# SCH_PWR.net
KiCad netlist of a schematic drawn in Altium Designer
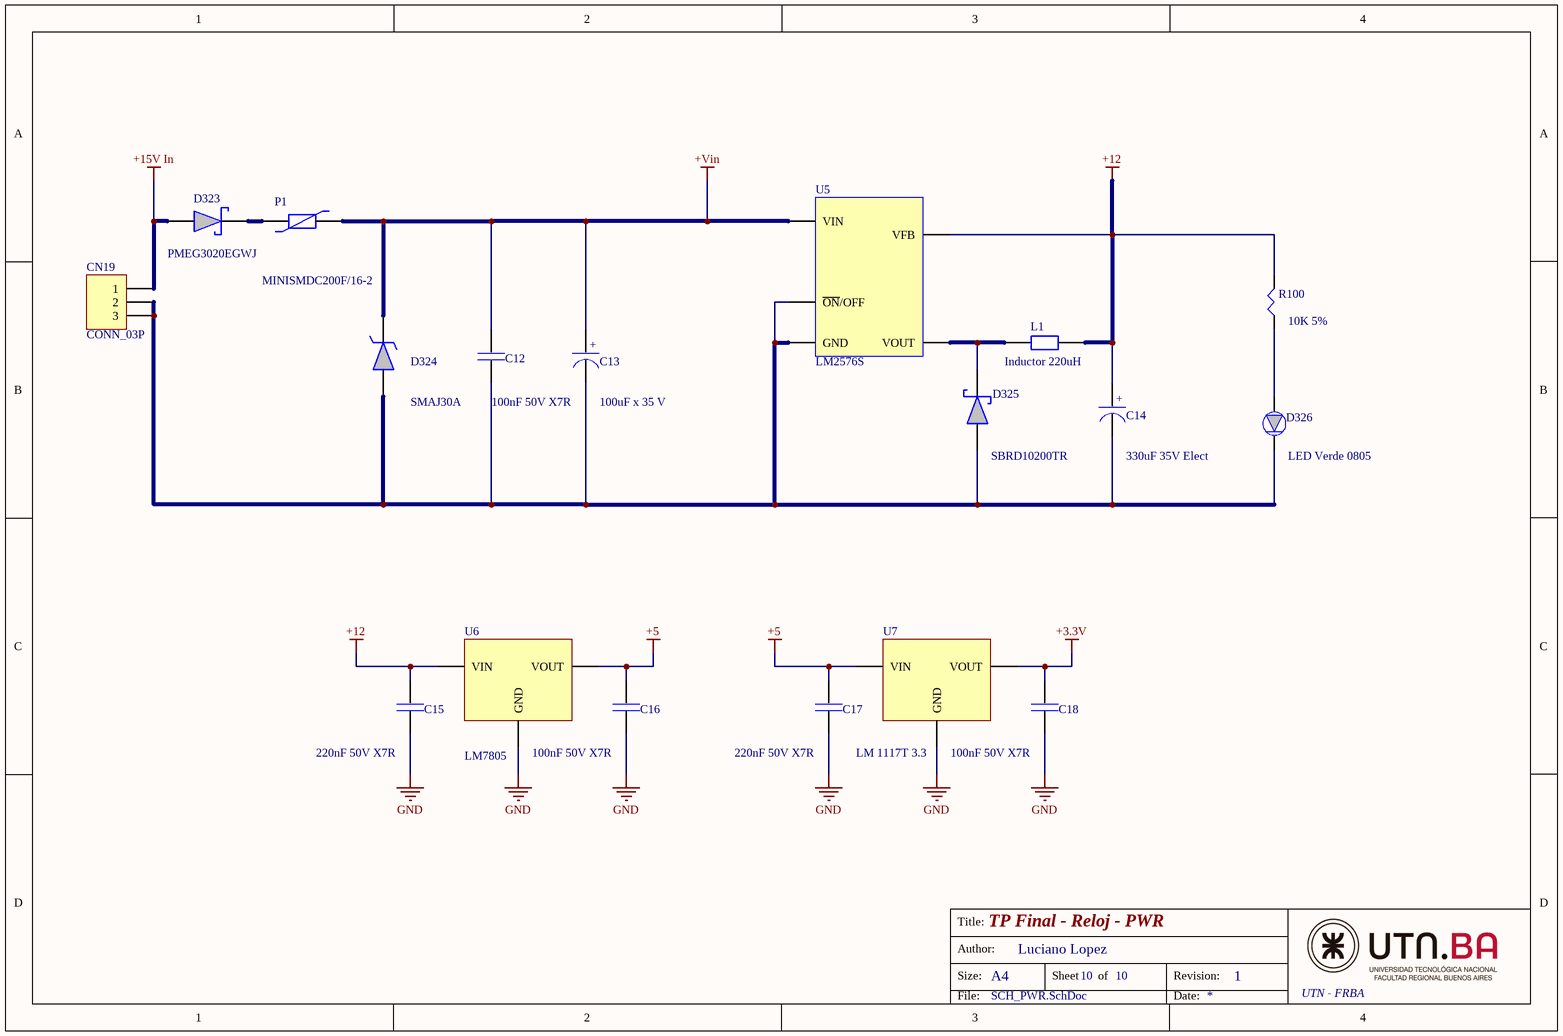
[diagram p0: SCH_PWR.SchDoc]

(export (version "E")
  (design (tool "Eeschema 10.0.6"))
  (components
    (comp (ref "C12")
      (value "100nF 50V X7R")
      (footprint "C_0805")
      (description "Capacitor ceramico 100nF x 50v")
      (libsource (lib "IDCI_WifiNode_2_R00") (part "Capacitor"))
    )
    (comp (ref "C13")
      (value "100uF x 35 V")
      (footprint "C_220ufx35V")
      (description "Capacitor Polarizado EEE-FK1V101P")
      (libsource (lib "IDCI_WifiNode_2_R00") (part "POL_CAP"))
    )
    (comp (ref "C14")
      (value "330uF 35V Elect")
      (footprint "C_220ufx35V")
      (description "Capacitor polarizado EMVY250ADA331MHA0G")
      (libsource (lib "IDCI_WifiNode_2_R00") (part "POL_CAP"))
    )
    (comp (ref "C15")
      (value "220nF 50V X7R")
      (footprint "C_0805")
      (description "Capacitor ceramico 100nF x 50v")
      (libsource (lib "IDCI_WifiNode_2_R00") (part "Capacitor"))
    )
    (comp (ref "C16")
      (value "100nF 50V X7R")
      (footprint "C_0805")
      (description "Capacitor ceramico 100nF x 50v")
      (libsource (lib "IDCI_WifiNode_2_R00") (part "Capacitor"))
    )
    (comp (ref "C17")
      (value "220nF 50V X7R")
      (footprint "C_0805")
      (description "Capacitor ceramico 100nF x 50v")
      (libsource (lib "IDCI_WifiNode_2_R00") (part "Capacitor"))
    )
    (comp (ref "C18")
      (value "100nF 50V X7R")
      (footprint "C_0805")
      (description "Capacitor ceramico 100nF x 50v")
      (libsource (lib "IDCI_WifiNode_2_R00") (part "Capacitor"))
    )
    (comp (ref "CN19")
      (value "CONN_03P")
      (footprint "JACK_2.5mm_F")
      (description "Connector Generic 3 Vias")
      (libsource (lib "IDCI_WifiNode_2_R00") (part "CONN_03P"))
    )
    (comp (ref "D323")
      (value "PMEG3020EGWJ")
      (description "Diodo Schottky")
      (libsource (lib "SCH_LIB") (part "SCHOTTKY_DIODE"))
    )
    (comp (ref "D324")
      (value "SMAJ30A")
      (description "Diodo supresor")
      (libsource (lib "SCH_LIB") (part "TVS_DIODE"))
    )
    (comp (ref "D325")
      (value "SBRD10200TR")
      (description "Diodo Schottky SBRD10200TR")
      (libsource (lib "SCH_LIB") (part "SCHOTTKY_DIODE"))
    )
    (comp (ref "D326")
      (value "LED Verde 0805")
      (footprint "LED_0805")
      (description "LED rojo 0805")
      (libsource (lib "SCH_LIB") (part "LED_DIODE"))
    )
    (comp (ref "L1")
      (value "Inductor 220uH")
      (description "732-11717-ND")
      (libsource (lib "SCH_LIB") (part "Inductor"))
    )
    (comp (ref "P1")
      (value "MINISMDC200F/16-2")
      (description "Polyswitch")
      (libsource (lib "SCH_LIB") (part "Polyswitch"))
    )
    (comp (ref "R100") (value "10K 5%") (footprint "R_0805") (libsource (lib "SCH_LIB") (part "Resistor")))
    (comp (ref "U5")
      (value "LM2576S")
      (description "Driver Switching")
      (libsource (lib "SCH_LIB") (part "Integrado-LM2576S"))
    )
    (comp (ref "U6")
      (value "LM7805")
      (description "Regulador Lineal")
      (libsource (lib "SCH_LIB") (part "Linear_Regulator"))
    )
    (comp (ref "U7")
      (value "LM 1117T 3.3")
      (description "Regulador Lineal")
      (libsource (lib "SCH_LIB") (part "Linear_Regulator"))
    )
  )
  (nets
    (net (code "1") (name "+3.3V") (class "Default")
      (node (ref "C18") (pin "1") (pinfunction "1_1") (pintype "passive"))
      (node (ref "U7") (pin "3") (pinfunction "VOUT_3") (pintype "passive"))
    )
    (net (code "2") (name "+5") (class "Default")
      (node (ref "C16") (pin "1") (pinfunction "1_1") (pintype "passive"))
      (node (ref "C17") (pin "1") (pinfunction "1_1") (pintype "passive"))
      (node (ref "U6") (pin "3") (pinfunction "VOUT_3") (pintype "passive"))
      (node (ref "U7") (pin "1") (pinfunction "VIN_1") (pintype "passive"))
    )
    (net (code "3") (name "+12") (class "Default")
      (node (ref "C14") (pin "1") (pinfunction "1_1") (pintype "passive"))
      (node (ref "C15") (pin "1") (pinfunction "1_1") (pintype "passive"))
      (node (ref "L1") (pin "2") (pinfunction "2_2") (pintype "passive"))
      (node (ref "R100") (pin "2") (pinfunction "2_2") (pintype "passive"))
      (node (ref "U5") (pin "4") (pinfunction "VFB_4") (pintype "passive"))
      (node (ref "U6") (pin "1") (pinfunction "VIN_1") (pintype "passive"))
    )
    (net (code "4") (name "+15V In") (class "Default")
      (node (ref "CN19") (pin "1") (pinfunction "1_1") (pintype "passive"))
      (node (ref "D323") (pin "1") (pinfunction "1_1") (pintype "passive"))
    )
    (net (code "5") (name "+Vin") (class "Default")
      (node (ref "C12") (pin "1") (pinfunction "1_1") (pintype "passive"))
      (node (ref "C13") (pin "1") (pinfunction "1_1") (pintype "passive"))
      (node (ref "D324") (pin "2") (pinfunction "2_2") (pintype "passive"))
      (node (ref "P1") (pin "2") (pinfunction "2_2") (pintype "passive"))
      (node (ref "U5") (pin "1") (pinfunction "VIN_1") (pintype "passive"))
    )
    (net (code "6") (name "GND") (class "Default")
      (node (ref "C15") (pin "2") (pinfunction "2_2") (pintype "passive"))
      (node (ref "C16") (pin "2") (pinfunction "2_2") (pintype "passive"))
      (node (ref "C17") (pin "2") (pinfunction "2_2") (pintype "passive"))
      (node (ref "C18") (pin "2") (pinfunction "2_2") (pintype "passive"))
      (node (ref "U6") (pin "2") (pinfunction "GND_2") (pintype "passive"))
      (node (ref "U7") (pin "2") (pinfunction "GND_2") (pintype "passive"))
    )
    (net (code "7") (name "Net-(D323-Pad2)") (class "Default")
      (node (ref "D323") (pin "2") (pinfunction "2_2") (pintype "passive"))
      (node (ref "P1") (pin "1") (pinfunction "1_1") (pintype "passive"))
    )
    (net (code "8") (name "Net-(D326-Pad1)") (class "Default")
      (node (ref "D326") (pin "1") (pinfunction "1_1") (pintype "passive"))
      (node (ref "R100") (pin "1") (pinfunction "1_1") (pintype "passive"))
    )
    (net (code "9") (name "Net-(U5-GND)") (class "Default")
      (node (ref "C12") (pin "2") (pinfunction "2_2") (pintype "passive"))
      (node (ref "C13") (pin "2") (pinfunction "2_2") (pintype "passive"))
      (node (ref "C14") (pin "2") (pinfunction "2_2") (pintype "passive"))
      (node (ref "CN19") (pin "2") (pinfunction "2_2") (pintype "passive"))
      (node (ref "CN19") (pin "3") (pinfunction "3_3") (pintype "passive"))
      (node (ref "D324") (pin "1") (pinfunction "1_1") (pintype "passive"))
      (node (ref "D325") (pin "1") (pinfunction "1_1") (pintype "passive"))
      (node (ref "D326") (pin "2") (pinfunction "2_2") (pintype "passive"))
      (node (ref "U5") (pin "3") (pinfunction "GND_3") (pintype "passive"))
      (node (ref "U5") (pin "5") (pinfunction "~{ON}/OFF_5") (pintype "passive"))
    )
    (net (code "10") (name "Net-(U5-VOUT)") (class "Default")
      (node (ref "D325") (pin "2") (pinfunction "2_2") (pintype "passive"))
      (node (ref "L1") (pin "1") (pinfunction "1_1") (pintype "passive"))
      (node (ref "U5") (pin "2") (pinfunction "VOUT_2") (pintype "passive"))
    )
  )
)
